# DSP28335.net
KiCad netlist of a schematic drawn in Altium Designer
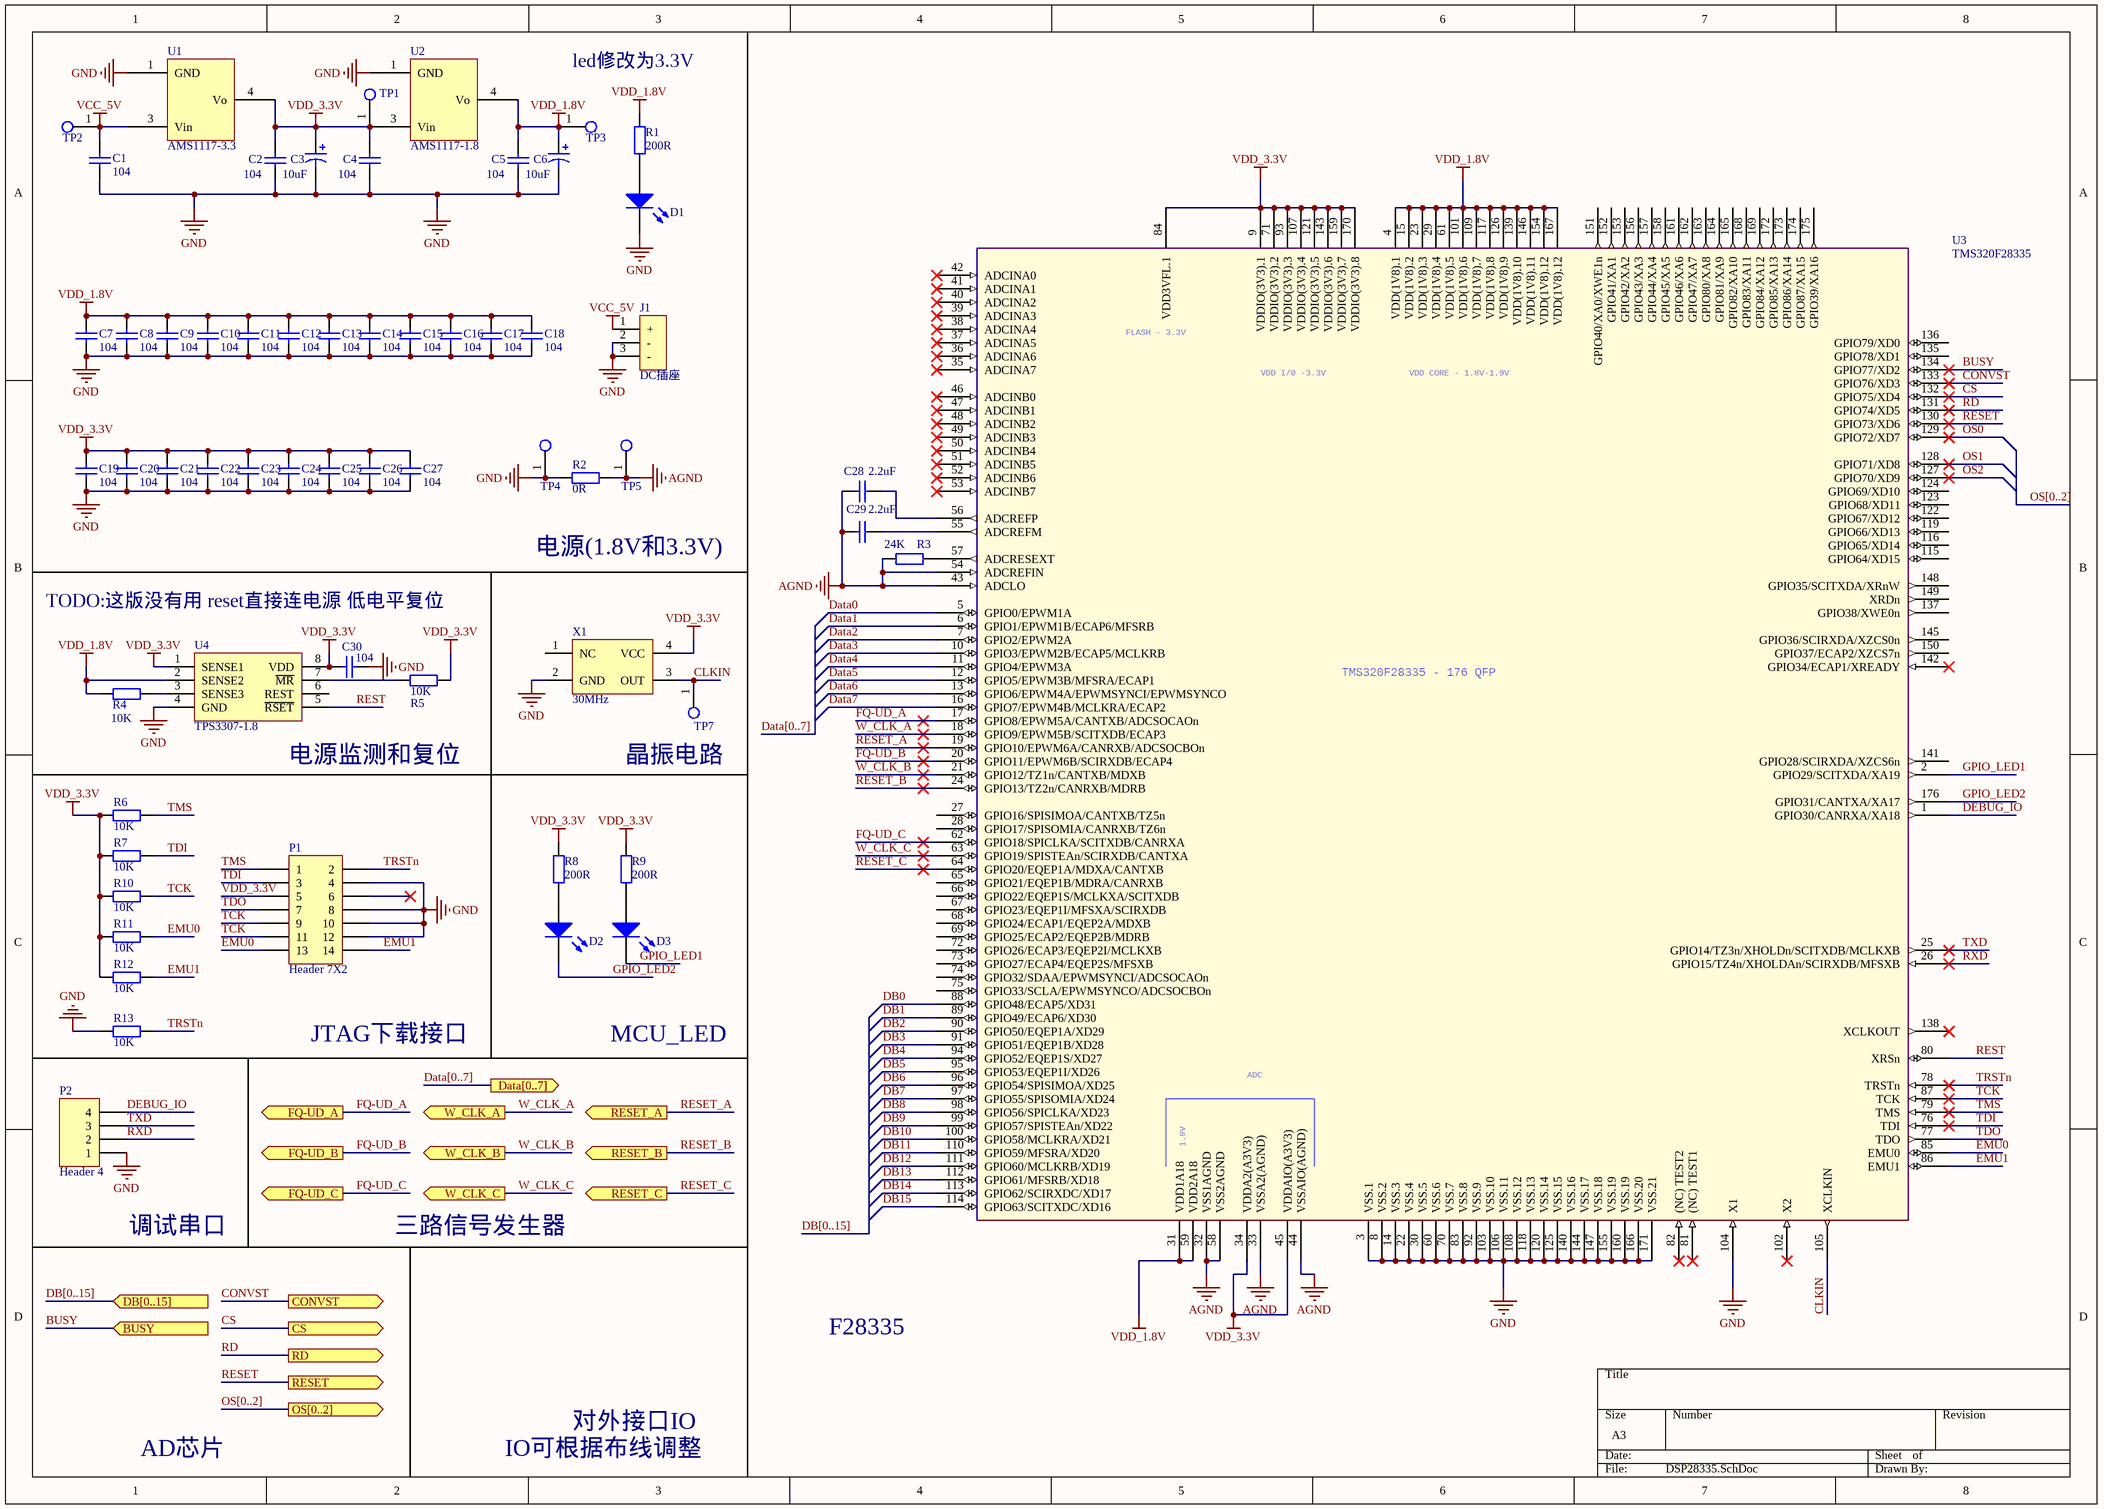
[diagram p0: DSP28335.SchDoc]

(export (version "E")
  (design (tool "Eeschema 10.0.6"))
  (components
    (comp (ref "C1")
      (value "104")
      (footprint "0603")
      (fields (field (name "Comment") "Cap"))
      (libsource (lib "自动化研究所集成库20170318") (part "Cap"))
    )
    (comp (ref "C2")
      (value "104")
      (footprint "0603")
      (fields (field (name "Comment") "Cap"))
      (libsource (lib "自动化研究所集成库20170318") (part "Cap"))
    )
    (comp (ref "C3")
      (value "10uF")
      (footprint "Cap 3528B")
      (fields (field (name "Comment") "Cap Poll"))
      (libsource (lib "自动化研究所集成库20170318") (part "Cap Poll"))
    )
    (comp (ref "C4")
      (value "104")
      (footprint "0603")
      (fields (field (name "Comment") "Cap"))
      (libsource (lib "自动化研究所集成库20170318") (part "Cap"))
    )
    (comp (ref "C5")
      (value "104")
      (footprint "0603")
      (fields (field (name "Comment") "Cap"))
      (libsource (lib "自动化研究所集成库20170318") (part "Cap"))
    )
    (comp (ref "C6")
      (value "10uF")
      (footprint "Cap 3528B")
      (fields (field (name "Comment") "Cap Poll"))
      (libsource (lib "自动化研究所集成库20170318") (part "Cap Poll"))
    )
    (comp (ref "C7")
      (value "104")
      (footprint "0603")
      (fields (field (name "Comment") "Cap"))
      (libsource (lib "自动化研究所集成库20170318") (part "Cap"))
    )
    (comp (ref "C8")
      (value "104")
      (footprint "0603")
      (fields (field (name "Comment") "Cap"))
      (libsource (lib "自动化研究所集成库20170318") (part "Cap"))
    )
    (comp (ref "C9")
      (value "104")
      (footprint "0603")
      (fields (field (name "Comment") "Cap"))
      (libsource (lib "自动化研究所集成库20170318") (part "Cap"))
    )
    (comp (ref "C10")
      (value "104")
      (footprint "0603")
      (fields (field (name "Comment") "Cap"))
      (libsource (lib "自动化研究所集成库20170318") (part "Cap"))
    )
    (comp (ref "C11")
      (value "104")
      (footprint "0603")
      (fields (field (name "Comment") "Cap"))
      (libsource (lib "自动化研究所集成库20170318") (part "Cap"))
    )
    (comp (ref "C12")
      (value "104")
      (footprint "0603")
      (fields (field (name "Comment") "Cap"))
      (libsource (lib "自动化研究所集成库20170318") (part "Cap"))
    )
    (comp (ref "C13")
      (value "104")
      (footprint "0603")
      (fields (field (name "Comment") "Cap"))
      (libsource (lib "自动化研究所集成库20170318") (part "Cap"))
    )
    (comp (ref "C14")
      (value "104")
      (footprint "0603")
      (fields (field (name "Comment") "Cap"))
      (libsource (lib "自动化研究所集成库20170318") (part "Cap"))
    )
    (comp (ref "C15")
      (value "104")
      (footprint "0603")
      (fields (field (name "Comment") "Cap"))
      (libsource (lib "自动化研究所集成库20170318") (part "Cap"))
    )
    (comp (ref "C16")
      (value "104")
      (footprint "0603")
      (fields (field (name "Comment") "Cap"))
      (libsource (lib "自动化研究所集成库20170318") (part "Cap"))
    )
    (comp (ref "C17")
      (value "104")
      (footprint "0603")
      (fields (field (name "Comment") "Cap"))
      (libsource (lib "自动化研究所集成库20170318") (part "Cap"))
    )
    (comp (ref "C18")
      (value "104")
      (footprint "0603")
      (fields (field (name "Comment") "Cap"))
      (libsource (lib "自动化研究所集成库20170318") (part "Cap"))
    )
    (comp (ref "C19")
      (value "104")
      (footprint "0603")
      (fields (field (name "Comment") "Cap"))
      (libsource (lib "自动化研究所集成库20170318") (part "Cap"))
    )
    (comp (ref "C20")
      (value "104")
      (footprint "0603")
      (fields (field (name "Comment") "Cap"))
      (libsource (lib "自动化研究所集成库20170318") (part "Cap"))
    )
    (comp (ref "C21")
      (value "104")
      (footprint "0603")
      (fields (field (name "Comment") "Cap"))
      (libsource (lib "自动化研究所集成库20170318") (part "Cap"))
    )
    (comp (ref "C22")
      (value "104")
      (footprint "0603")
      (fields (field (name "Comment") "Cap"))
      (libsource (lib "自动化研究所集成库20170318") (part "Cap"))
    )
    (comp (ref "C23")
      (value "104")
      (footprint "0603")
      (fields (field (name "Comment") "Cap"))
      (libsource (lib "自动化研究所集成库20170318") (part "Cap"))
    )
    (comp (ref "C24")
      (value "104")
      (footprint "0603")
      (fields (field (name "Comment") "Cap"))
      (libsource (lib "自动化研究所集成库20170318") (part "Cap"))
    )
    (comp (ref "C25")
      (value "104")
      (footprint "0603")
      (fields (field (name "Comment") "Cap"))
      (libsource (lib "自动化研究所集成库20170318") (part "Cap"))
    )
    (comp (ref "C26")
      (value "104")
      (footprint "0603")
      (fields (field (name "Comment") "Cap"))
      (libsource (lib "自动化研究所集成库20170318") (part "Cap"))
    )
    (comp (ref "C27")
      (value "104")
      (footprint "0603")
      (fields (field (name "Comment") "Cap"))
      (libsource (lib "自动化研究所集成库20170318") (part "Cap"))
    )
    (comp (ref "C28")
      (value "2.2uF")
      (footprint "0603")
      (fields (field (name "Comment") "Cap"))
      (libsource (lib "自动化研究所集成库20170318") (part "Cap"))
    )
    (comp (ref "C29")
      (value "2.2uF")
      (footprint "0603")
      (fields (field (name "Comment") "Cap"))
      (libsource (lib "自动化研究所集成库20170318") (part "Cap"))
    )
    (comp (ref "C30")
      (value "104")
      (footprint "0603")
      (fields (field (name "Comment") "Cap"))
      (libsource (lib "自动化研究所集成库20170318") (part "Cap"))
    )
    (comp (ref "D1") (value "LED") (footprint "LED0603") (libsource (lib "自动化研究所集成库20170318") (part "LED")))
    (comp (ref "D2") (value "LED") (footprint "LED0603") (libsource (lib "自动化研究所集成库20170318") (part "LED")))
    (comp (ref "D3") (value "LED") (footprint "LED0603") (libsource (lib "自动化研究所集成库20170318") (part "LED")))
    (comp (ref "J1")
      (value "DC插座")
      (footprint "DC插座 5.5mm*2.1mm")
      (libsource (lib "自动化研究所集成库20170318") (part "DC插座"))
    )
    (comp (ref "P1")
      (value "Header 7X2")
      (footprint "HDR2X7")
      (description "Header, 7-Pin, Dual row")
      (libsource (lib "Miscellaneous Connectors") (part "Header 7X2"))
    )
    (comp (ref "P2")
      (value "Header 4")
      (footprint "HDR1X4")
      (description "Header, 4-Pin")
      (libsource (lib "Miscellaneous Connectors") (part "Header 4"))
    )
    (comp (ref "R1")
      (value "200R")
      (footprint "0603")
      (fields (field (name "Comment") "Res"))
      (libsource (lib "") (part "Res_3"))
    )
    (comp (ref "R2")
      (value "0R")
      (footprint "0603")
      (fields (field (name "Comment") "Res"))
      (libsource (lib "") (part "Res_2"))
    )
    (comp (ref "R3")
      (value "24K")
      (footprint "0603")
      (fields (field (name "Comment") "Res"))
      (libsource (lib "自动化研究所集成库20170318") (part "Res"))
    )
    (comp (ref "R4")
      (value "10K")
      (footprint "0603")
      (fields (field (name "Comment") "Res"))
      (libsource (lib "") (part "Res_2"))
    )
    (comp (ref "R5")
      (value "10K")
      (footprint "0603")
      (fields (field (name "Comment") "Res"))
      (libsource (lib "自动化研究所集成库20170318") (part "Res"))
    )
    (comp (ref "R6")
      (value "10K")
      (footprint "0603")
      (fields (field (name "Comment") "Res"))
      (libsource (lib "自动化研究所集成库20170318") (part "Res"))
    )
    (comp (ref "R7")
      (value "10K")
      (footprint "0603")
      (fields (field (name "Comment") "Res"))
      (libsource (lib "自动化研究所集成库20170318") (part "Res"))
    )
    (comp (ref "R8")
      (value "200R")
      (footprint "0603")
      (fields (field (name "Comment") "Res"))
      (libsource (lib "") (part "Res_1"))
    )
    (comp (ref "R9")
      (value "200R")
      (footprint "0603")
      (fields (field (name "Comment") "Res"))
      (libsource (lib "") (part "Res_1"))
    )
    (comp (ref "R10")
      (value "10K")
      (footprint "0603")
      (fields (field (name "Comment") "Res"))
      (libsource (lib "自动化研究所集成库20170318") (part "Res"))
    )
    (comp (ref "R11")
      (value "10K")
      (footprint "0603")
      (fields (field (name "Comment") "Res"))
      (libsource (lib "自动化研究所集成库20170318") (part "Res"))
    )
    (comp (ref "R12")
      (value "10K")
      (footprint "0603")
      (fields (field (name "Comment") "Res"))
      (libsource (lib "自动化研究所集成库20170318") (part "Res"))
    )
    (comp (ref "R13")
      (value "10K")
      (footprint "0603")
      (fields (field (name "Comment") "Res"))
      (libsource (lib "自动化研究所集成库20170318") (part "Res"))
    )
    (comp (ref "TP1") (value "testPoint") (footprint "TP_H") (libsource (lib "Spartan") (part "TP")))
    (comp (ref "TP2") (value "testPoint") (footprint "TP_H") (libsource (lib "Spartan") (part "TP")))
    (comp (ref "TP3") (value "testPoint") (footprint "TP_H") (libsource (lib "Spartan") (part "TP")))
    (comp (ref "TP4") (value "testPoint") (footprint "TP_H") (libsource (lib "Spartan") (part "TP")))
    (comp (ref "TP5") (value "testPoint") (footprint "TP_H") (libsource (lib "Spartan") (part "TP")))
    (comp (ref "TP7") (value "testPoint") (footprint "TP_H") (libsource (lib "Spartan") (part "TP")))
    (comp (ref "U1")
      (value "AMS1117-3.3")
      (footprint "TO-252-2L")
      (libsource (lib "Spartan") (part "AMS1117"))
    )
    (comp (ref "U2")
      (value "AMS1117-1.8")
      (footprint "TO-252-2L")
      (libsource (lib "Spartan") (part "AMS1117"))
    )
    (comp (ref "U3")
      (value "TMS320F28335")
      (footprint "TMS320F28335")
      (libsource (lib "DuGu") (part "TMS320F28335"))
    )
    (comp (ref "U4") (value "TPS3307-1.8") (footprint "SOP-8") (libsource (lib "Dugu") (part "TPS3307-1.8")))
    (comp (ref "X1")
      (value "30MHz")
      (footprint "3225")
      (libsource (lib "PulsePower-Buck") (part "Oscillator"))
    )
  )
  (nets
    (net (code "1") (name "/BUSY") (class "Default")
      (node (ref "U3") (pin "134") (pinfunction "GPIO77/XD2_134") (pintype "bidirectional+no_connect"))
    )
    (net (code "2") (name "/CLKIN") (class "Default")
      (node (ref "TP7") (pin "1") (pinfunction "1_1") (pintype "passive"))
      (node (ref "U3") (pin "105") (pinfunction "XCLKIN_105") (pintype "output"))
      (node (ref "X1") (pin "3") (pinfunction "OUT_3") (pintype "passive"))
    )
    (net (code "3") (name "/CONVST") (class "Default")
      (node (ref "U3") (pin "133") (pinfunction "GPIO76/XD3_133") (pintype "bidirectional+no_connect"))
    )
    (net (code "4") (name "/CS") (class "Default")
      (node (ref "U3") (pin "132") (pinfunction "GPIO75/XD4_132") (pintype "bidirectional+no_connect"))
    )
    (net (code "5") (name "/DB0") (class "Default")
      (node (ref "U3") (pin "88") (pinfunction "GPIO48/ECAP5/XD31_88") (pintype "bidirectional"))
    )
    (net (code "6") (name "/DB1") (class "Default")
      (node (ref "U3") (pin "89") (pinfunction "GPIO49/ECAP6/XD30_89") (pintype "bidirectional"))
    )
    (net (code "7") (name "/DB2") (class "Default")
      (node (ref "U3") (pin "90") (pinfunction "GPIO50/EQEP1A/XD29_90") (pintype "bidirectional"))
    )
    (net (code "8") (name "/DB3") (class "Default")
      (node (ref "U3") (pin "91") (pinfunction "GPIO51/EQEP1B/XD28_91") (pintype "bidirectional"))
    )
    (net (code "9") (name "/DB4") (class "Default")
      (node (ref "U3") (pin "94") (pinfunction "GPIO52/EQEP1S/XD27_94") (pintype "bidirectional"))
    )
    (net (code "10") (name "/DB5") (class "Default")
      (node (ref "U3") (pin "95") (pinfunction "GPIO53/EQEP1I/XD26_95") (pintype "bidirectional"))
    )
    (net (code "11") (name "/DB6") (class "Default")
      (node (ref "U3") (pin "96") (pinfunction "GPIO54/SPISIMOA/XD25_96") (pintype "bidirectional"))
    )
    (net (code "12") (name "/DB7") (class "Default")
      (node (ref "U3") (pin "97") (pinfunction "GPIO55/SPISOMIA/XD24_97") (pintype "bidirectional"))
    )
    (net (code "13") (name "/DB8") (class "Default")
      (node (ref "U3") (pin "98") (pinfunction "GPIO56/SPICLKA/XD23_98") (pintype "bidirectional"))
    )
    (net (code "14") (name "/DB9") (class "Default")
      (node (ref "U3") (pin "99") (pinfunction "GPIO57/SPISTEAn/XD22_99") (pintype "bidirectional"))
    )
    (net (code "15") (name "/DB10") (class "Default")
      (node (ref "U3") (pin "100") (pinfunction "GPIO58/MCLKRA/XD21_100") (pintype "bidirectional"))
    )
    (net (code "16") (name "/DB11") (class "Default")
      (node (ref "U3") (pin "110") (pinfunction "GPIO59/MFSRA/XD20_110") (pintype "bidirectional"))
    )
    (net (code "17") (name "/DB12") (class "Default")
      (node (ref "U3") (pin "111") (pinfunction "GPIO60/MCLKRB/XD19_111") (pintype "bidirectional"))
    )
    (net (code "18") (name "/DB13") (class "Default")
      (node (ref "U3") (pin "112") (pinfunction "GPIO61/MFSRB/XD18_112") (pintype "bidirectional"))
    )
    (net (code "19") (name "/DB14") (class "Default")
      (node (ref "U3") (pin "113") (pinfunction "GPIO62/SCIRXDC/XD17_113") (pintype "bidirectional"))
    )
    (net (code "20") (name "/DB15") (class "Default")
      (node (ref "U3") (pin "114") (pinfunction "GPIO63/SCITXDC/XD16_114") (pintype "bidirectional"))
    )
    (net (code "22") (name "/DEBUG_IO") (class "Default")
      (node (ref "P2") (pin "4") (pinfunction "4_4") (pintype "passive"))
      (node (ref "U3") (pin "1") (pinfunction "GPIO30/CANRXA/XA18_1") (pintype "output"))
    )
    (net (code "23") (name "/Data0") (class "Default")
      (node (ref "U3") (pin "5") (pinfunction "GPIO0/EPWM1A_5") (pintype "bidirectional"))
    )
    (net (code "24") (name "/Data1") (class "Default")
      (node (ref "U3") (pin "6") (pinfunction "GPIO1/EPWM1B/ECAP6/MFSRB_6") (pintype "bidirectional"))
    )
    (net (code "25") (name "/Data2") (class "Default")
      (node (ref "U3") (pin "7") (pinfunction "GPIO2/EPWM2A_7") (pintype "bidirectional"))
    )
    (net (code "26") (name "/Data3") (class "Default")
      (node (ref "U3") (pin "10") (pinfunction "GPIO3/EPWM2B/ECAP5/MCLKRB_10") (pintype "bidirectional"))
    )
    (net (code "27") (name "/Data4") (class "Default")
      (node (ref "U3") (pin "11") (pinfunction "GPIO4/EPWM3A_11") (pintype "bidirectional"))
    )
    (net (code "28") (name "/Data5") (class "Default")
      (node (ref "U3") (pin "12") (pinfunction "GPIO5/EPWM3B/MFSRA/ECAP1_12") (pintype "bidirectional"))
    )
    (net (code "29") (name "/Data6") (class "Default")
      (node (ref "U3") (pin "13") (pinfunction "GPIO6/EPWM4A/EPWMSYNCI/EPWMSYNCO_13") (pintype "bidirectional"))
    )
    (net (code "30") (name "/Data7") (class "Default")
      (node (ref "U3") (pin "16") (pinfunction "GPIO7/EPWM4B/MCLKRA/ECAP2_16") (pintype "bidirectional"))
    )
    (net (code "32") (name "/EMU0") (class "Default")
      (node (ref "P1") (pin "13") (pinfunction "13_13") (pintype "passive"))
      (node (ref "R11") (pin "2") (pinfunction "2_2") (pintype "passive"))
      (node (ref "U3") (pin "85") (pinfunction "EMU0_85") (pintype "bidirectional"))
    )
    (net (code "33") (name "/EMU1") (class "Default")
      (node (ref "P1") (pin "14") (pinfunction "14_14") (pintype "passive"))
      (node (ref "R12") (pin "2") (pinfunction "2_2") (pintype "passive"))
      (node (ref "U3") (pin "86") (pinfunction "EMU1_86") (pintype "bidirectional"))
    )
    (net (code "34") (name "/FQ-UD_A") (class "Default")
      (node (ref "U3") (pin "17") (pinfunction "GPIO8/EPWM5A/CANTXB/ADCSOCAOn_17") (pintype "bidirectional"))
    )
    (net (code "35") (name "/FQ-UD_B") (class "Default")
      (node (ref "U3") (pin "20") (pinfunction "GPIO11/EPWM6B/SCIRXDB/ECAP4_20") (pintype "bidirectional"))
    )
    (net (code "36") (name "/FQ-UD_C") (class "Default")
      (node (ref "U3") (pin "62") (pinfunction "GPIO18/SPICLKA/SCITXDB/CANRXA_62") (pintype "bidirectional"))
    )
    (net (code "37") (name "/GPIO_LED1") (class "Default")
      (node (ref "D3") (pin "2") (pinfunction "K_2") (pintype "passive"))
      (node (ref "U3") (pin "2") (pinfunction "GPIO29/SCITXDA/XA19_2") (pintype "output"))
    )
    (net (code "38") (name "/GPIO_LED2") (class "Default")
      (node (ref "D2") (pin "2") (pinfunction "K_2") (pintype "passive"))
      (node (ref "U3") (pin "176") (pinfunction "GPIO31/CANTXA/XA17_176") (pintype "output"))
    )
    (net (code "39") (name "/OS0") (class "Default")
      (node (ref "U3") (pin "129") (pinfunction "GPIO72/XD7_129") (pintype "bidirectional+no_connect"))
    )
    (net (code "40") (name "/OS1") (class "Default")
      (node (ref "U3") (pin "128") (pinfunction "GPIO71/XD8_128") (pintype "bidirectional+no_connect"))
    )
    (net (code "41") (name "/OS2") (class "Default")
      (node (ref "U3") (pin "127") (pinfunction "GPIO70/XD9_127") (pintype "bidirectional+no_connect"))
    )
    (net (code "43") (name "/RD") (class "Default")
      (node (ref "U3") (pin "131") (pinfunction "GPIO74/XD5_131") (pintype "bidirectional+no_connect"))
    )
    (net (code "44") (name "/RESET") (class "Default")
      (node (ref "U3") (pin "130") (pinfunction "GPIO73/XD6_130") (pintype "bidirectional+no_connect"))
    )
    (net (code "45") (name "/RESET_A") (class "Default")
      (node (ref "U3") (pin "19") (pinfunction "GPIO10/EPWM6A/CANRXB/ADCSOCBOn_19") (pintype "bidirectional"))
    )
    (net (code "46") (name "/RESET_B") (class "Default")
      (node (ref "U3") (pin "24") (pinfunction "GPIO13/TZ2n/CANRXB/MDRB_24") (pintype "bidirectional"))
    )
    (net (code "47") (name "/RESET_C") (class "Default")
      (node (ref "U3") (pin "64") (pinfunction "GPIO20/EQEP1A/MDXA/CANTXB_64") (pintype "bidirectional"))
    )
    (net (code "48") (name "/REST") (class "Default")
      (node (ref "U3") (pin "80") (pinfunction "XRSn_80") (pintype "bidirectional"))
      (node (ref "U4") (pin "5") (pinfunction "~{RSET}_5") (pintype "passive"))
    )
    (net (code "49") (name "/RXD") (class "Default")
      (node (ref "P2") (pin "2") (pinfunction "2_2") (pintype "passive"))
      (node (ref "U3") (pin "26") (pinfunction "GPIO15/TZ4n/XHOLDAn/SCIRXDB/MFSXB_26") (pintype "input"))
    )
    (net (code "50") (name "/TCK") (class "Default")
      (node (ref "P1") (pin "11") (pinfunction "11_11") (pintype "passive"))
      (node (ref "P1") (pin "9") (pinfunction "9_9") (pintype "passive"))
      (node (ref "R10") (pin "2") (pinfunction "2_2") (pintype "passive"))
      (node (ref "U3") (pin "87") (pinfunction "TCK_87") (pintype "input"))
    )
    (net (code "51") (name "/TDI") (class "Default")
      (node (ref "P1") (pin "3") (pinfunction "3_3") (pintype "passive"))
      (node (ref "R7") (pin "2") (pinfunction "2_2") (pintype "passive"))
      (node (ref "U3") (pin "76") (pinfunction "TDI_76") (pintype "input"))
    )
    (net (code "52") (name "/TDO") (class "Default")
      (node (ref "P1") (pin "7") (pinfunction "7_7") (pintype "passive"))
      (node (ref "U3") (pin "77") (pinfunction "TDO_77") (pintype "output"))
    )
    (net (code "53") (name "/TMS") (class "Default")
      (node (ref "P1") (pin "1") (pinfunction "1_1") (pintype "passive"))
      (node (ref "R6") (pin "2") (pinfunction "2_2") (pintype "passive"))
      (node (ref "U3") (pin "79") (pinfunction "TMS_79") (pintype "input"))
    )
    (net (code "54") (name "/TRSTn") (class "Default")
      (node (ref "P1") (pin "2") (pinfunction "2_2") (pintype "passive"))
      (node (ref "R13") (pin "2") (pinfunction "2_2") (pintype "passive"))
      (node (ref "U3") (pin "78") (pinfunction "TRSTn_78") (pintype "input"))
    )
    (net (code "55") (name "/TXD") (class "Default")
      (node (ref "P2") (pin "3") (pinfunction "3_3") (pintype "passive"))
      (node (ref "U3") (pin "25") (pinfunction "GPIO14/TZ3n/XHOLDn/SCITXDB/MCLKXB_25") (pintype "output"))
    )
    (net (code "56") (name "/W_CLK_A") (class "Default")
      (node (ref "U3") (pin "18") (pinfunction "GPIO9/EPWM5B/SCITXDB/ECAP3_18") (pintype "bidirectional"))
    )
    (net (code "57") (name "/W_CLK_B") (class "Default")
      (node (ref "U3") (pin "21") (pinfunction "GPIO12/TZ1n/CANTXB/MDXB_21") (pintype "bidirectional"))
    )
    (net (code "58") (name "/W_CLK_C") (class "Default")
      (node (ref "U3") (pin "63") (pinfunction "GPIO19/SPISTEAn/SCIRXDB/CANTXA_63") (pintype "bidirectional"))
    )
    (net (code "59") (name "AGND") (class "Default")
      (node (ref "C28") (pin "2") (pinfunction "2_2") (pintype "passive"))
      (node (ref "C29") (pin "2") (pinfunction "2_2") (pintype "passive"))
      (node (ref "R2") (pin "1") (pinfunction "1_1") (pintype "passive"))
      (node (ref "R3") (pin "1") (pinfunction "1_1") (pintype "passive"))
      (node (ref "TP5") (pin "1") (pinfunction "1_1") (pintype "passive"))
      (node (ref "U3") (pin "32") (pinfunction "VSS1AGND_32") (pintype "power_in"))
      (node (ref "U3") (pin "33") (pinfunction "VSSA2(AGND)_33") (pintype "power_in"))
      (node (ref "U3") (pin "43") (pinfunction "ADCLO_43") (pintype "input"))
      (node (ref "U3") (pin "44") (pinfunction "VSSAIO(AGND)_44") (pintype "power_in"))
      (node (ref "U3") (pin "54") (pinfunction "ADCREFIN_54") (pintype "input"))
      (node (ref "U3") (pin "58") (pinfunction "VSS2AGND_58") (pintype "power_in"))
    )
    (net (code "60") (name "GND") (class "Default")
      (node (ref "C1") (pin "1") (pinfunction "1_1") (pintype "passive"))
      (node (ref "C10") (pin "1") (pinfunction "1_1") (pintype "passive"))
      (node (ref "C11") (pin "1") (pinfunction "1_1") (pintype "passive"))
      (node (ref "C12") (pin "1") (pinfunction "1_1") (pintype "passive"))
      (node (ref "C13") (pin "1") (pinfunction "1_1") (pintype "passive"))
      (node (ref "C14") (pin "1") (pinfunction "1_1") (pintype "passive"))
      (node (ref "C15") (pin "1") (pinfunction "1_1") (pintype "passive"))
      (node (ref "C16") (pin "1") (pinfunction "1_1") (pintype "passive"))
      (node (ref "C17") (pin "1") (pinfunction "1_1") (pintype "passive"))
      (node (ref "C18") (pin "1") (pinfunction "1_1") (pintype "passive"))
      (node (ref "C19") (pin "1") (pinfunction "1_1") (pintype "passive"))
      (node (ref "C2") (pin "1") (pinfunction "1_1") (pintype "passive"))
      (node (ref "C20") (pin "1") (pinfunction "1_1") (pintype "passive"))
      (node (ref "C21") (pin "1") (pinfunction "1_1") (pintype "passive"))
      (node (ref "C22") (pin "1") (pinfunction "1_1") (pintype "passive"))
      (node (ref "C23") (pin "1") (pinfunction "1_1") (pintype "passive"))
      (node (ref "C24") (pin "1") (pinfunction "1_1") (pintype "passive"))
      (node (ref "C25") (pin "1") (pinfunction "1_1") (pintype "passive"))
      (node (ref "C26") (pin "1") (pinfunction "1_1") (pintype "passive"))
      (node (ref "C27") (pin "1") (pinfunction "1_1") (pintype "passive"))
      (node (ref "C3") (pin "2") (pinfunction "2_2") (pintype "passive"))
      (node (ref "C30") (pin "1") (pinfunction "1_1") (pintype "passive"))
      (node (ref "C4") (pin "1") (pinfunction "1_1") (pintype "passive"))
      (node (ref "C5") (pin "1") (pinfunction "1_1") (pintype "passive"))
      (node (ref "C6") (pin "2") (pinfunction "2_2") (pintype "passive"))
      (node (ref "C7") (pin "1") (pinfunction "1_1") (pintype "passive"))
      (node (ref "C8") (pin "1") (pinfunction "1_1") (pintype "passive"))
      (node (ref "C9") (pin "1") (pinfunction "1_1") (pintype "passive"))
      (node (ref "D1") (pin "2") (pinfunction "K_2") (pintype "passive"))
      (node (ref "J1") (pin "2") (pinfunction "-_2") (pintype "power_in"))
      (node (ref "J1") (pin "3") (pinfunction "-_3") (pintype "power_in"))
      (node (ref "P1") (pin "10") (pinfunction "10_10") (pintype "passive"))
      (node (ref "P1") (pin "12") (pinfunction "12_12") (pintype "passive"))
      (node (ref "P1") (pin "4") (pinfunction "4_4") (pintype "passive"))
      (node (ref "P1") (pin "8") (pinfunction "8_8") (pintype "passive"))
      (node (ref "P2") (pin "1") (pinfunction "1_1") (pintype "passive"))
      (node (ref "R13") (pin "1") (pinfunction "1_1") (pintype "passive"))
      (node (ref "R2") (pin "2") (pinfunction "2_2") (pintype "passive"))
      (node (ref "TP4") (pin "1") (pinfunction "1_1") (pintype "passive"))
      (node (ref "U1") (pin "1") (pinfunction "GND_1") (pintype "passive"))
      (node (ref "U2") (pin "1") (pinfunction "GND_1") (pintype "passive"))
      (node (ref "U3") (pin "103") (pinfunction "VSS.10_103") (pintype "power_in"))
      (node (ref "U3") (pin "104") (pinfunction "X1_104") (pintype "input"))
      (node (ref "U3") (pin "106") (pinfunction "VSS.11_106") (pintype "power_in"))
      (node (ref "U3") (pin "108") (pinfunction "VSS.12_108") (pintype "power_in"))
      (node (ref "U3") (pin "118") (pinfunction "VSS.13_118") (pintype "power_in"))
      (node (ref "U3") (pin "120") (pinfunction "VSS.14_120") (pintype "power_in"))
      (node (ref "U3") (pin "125") (pinfunction "VSS.15_125") (pintype "power_in"))
      (node (ref "U3") (pin "14") (pinfunction "VSS.3_14") (pintype "power_in"))
      (node (ref "U3") (pin "140") (pinfunction "VSS.16_140") (pintype "power_in"))
      (node (ref "U3") (pin "144") (pinfunction "VSS.17_144") (pintype "power_in"))
      (node (ref "U3") (pin "147") (pinfunction "VSS.18_147") (pintype "power_in"))
      (node (ref "U3") (pin "155") (pinfunction "VSS.19_155") (pintype "power_in"))
      (node (ref "U3") (pin "160") (pinfunction "VSS.19_160") (pintype "power_in"))
      (node (ref "U3") (pin "166") (pinfunction "VSS.20_166") (pintype "power_in"))
      (node (ref "U3") (pin "171") (pinfunction "VSS.21_171") (pintype "power_in"))
      (node (ref "U3") (pin "22") (pinfunction "VSS.4_22") (pintype "power_in"))
      (node (ref "U3") (pin "3") (pinfunction "VSS.1_3") (pintype "power_in"))
      (node (ref "U3") (pin "30") (pinfunction "VSS.5_30") (pintype "power_in"))
      (node (ref "U3") (pin "60") (pinfunction "VSS.6_60") (pintype "power_in"))
      (node (ref "U3") (pin "70") (pinfunction "VSS.7_70") (pintype "power_in"))
      (node (ref "U3") (pin "8") (pinfunction "VSS.2_8") (pintype "power_in"))
      (node (ref "U3") (pin "83") (pinfunction "VSS.8_83") (pintype "power_in"))
      (node (ref "U3") (pin "92") (pinfunction "VSS.9_92") (pintype "power_in"))
      (node (ref "U4") (pin "4") (pinfunction "GND_4") (pintype "passive"))
      (node (ref "X1") (pin "2") (pinfunction "GND_2") (pintype "passive"))
    )
    (net (code "61") (name "Net-(D1-A)") (class "Default")
      (node (ref "D1") (pin "1") (pinfunction "A_1") (pintype "passive"))
      (node (ref "R1") (pin "1") (pinfunction "1_1") (pintype "passive"))
    )
    (net (code "62") (name "Net-(D2-A)") (class "Default")
      (node (ref "D2") (pin "1") (pinfunction "A_1") (pintype "passive"))
      (node (ref "R8") (pin "2") (pinfunction "2_2") (pintype "passive"))
    )
    (net (code "63") (name "Net-(D3-A)") (class "Default")
      (node (ref "D3") (pin "1") (pinfunction "A_1") (pintype "passive"))
      (node (ref "R9") (pin "2") (pinfunction "2_2") (pintype "passive"))
    )
    (net (code "64") (name "Net-(U3-ADCREFM)") (class "Default")
      (node (ref "C29") (pin "1") (pinfunction "1_1") (pintype "passive"))
      (node (ref "U3") (pin "55") (pinfunction "ADCREFM_55") (pintype "output"))
    )
    (net (code "65") (name "Net-(U3-ADCREFP)") (class "Default")
      (node (ref "C28") (pin "1") (pinfunction "1_1") (pintype "passive"))
      (node (ref "U3") (pin "56") (pinfunction "ADCREFP_56") (pintype "output"))
    )
    (net (code "66") (name "Net-(U3-ADCRESEXT)") (class "Default")
      (node (ref "R3") (pin "2") (pinfunction "2_2") (pintype "passive"))
      (node (ref "U3") (pin "57") (pinfunction "ADCRESEXT_57") (pintype "output"))
    )
    (net (code "67") (name "Net-(U4-SENSE3)") (class "Default")
      (node (ref "R4") (pin "1") (pinfunction "1_1") (pintype "passive"))
      (node (ref "U4") (pin "3") (pinfunction "SENSE3_3") (pintype "passive"))
    )
    (net (code "68") (name "Net-(U4-~{MR})") (class "Default")
      (node (ref "R5") (pin "1") (pinfunction "1_1") (pintype "passive"))
      (node (ref "U4") (pin "7") (pinfunction "~{MR}_7") (pintype "passive"))
    )
    (net (code "69") (name "VCC_5V") (class "Default")
      (node (ref "C1") (pin "2") (pinfunction "2_2") (pintype "passive"))
      (node (ref "J1") (pin "1") (pinfunction "+_1") (pintype "power_in"))
      (node (ref "TP2") (pin "1") (pinfunction "1_1") (pintype "passive"))
      (node (ref "U1") (pin "3") (pinfunction "Vin_3") (pintype "passive"))
    )
    (net (code "70") (name "VDD_1.8V") (class "Default")
      (node (ref "C10") (pin "2") (pinfunction "2_2") (pintype "passive"))
      (node (ref "C11") (pin "2") (pinfunction "2_2") (pintype "passive"))
      (node (ref "C12") (pin "2") (pinfunction "2_2") (pintype "passive"))
      (node (ref "C13") (pin "2") (pinfunction "2_2") (pintype "passive"))
      (node (ref "C14") (pin "2") (pinfunction "2_2") (pintype "passive"))
      (node (ref "C15") (pin "2") (pinfunction "2_2") (pintype "passive"))
      (node (ref "C16") (pin "2") (pinfunction "2_2") (pintype "passive"))
      (node (ref "C17") (pin "2") (pinfunction "2_2") (pintype "passive"))
      (node (ref "C18") (pin "2") (pinfunction "2_2") (pintype "passive"))
      (node (ref "C5") (pin "2") (pinfunction "2_2") (pintype "passive"))
      (node (ref "C6") (pin "1") (pinfunction "1_1") (pintype "passive"))
      (node (ref "C7") (pin "2") (pinfunction "2_2") (pintype "passive"))
      (node (ref "C8") (pin "2") (pinfunction "2_2") (pintype "passive"))
      (node (ref "C9") (pin "2") (pinfunction "2_2") (pintype "passive"))
      (node (ref "R1") (pin "2") (pinfunction "2_2") (pintype "passive"))
      (node (ref "R4") (pin "2") (pinfunction "2_2") (pintype "passive"))
      (node (ref "TP3") (pin "1") (pinfunction "1_1") (pintype "passive"))
      (node (ref "U2") (pin "4") (pinfunction "Vo_4") (pintype "passive"))
      (node (ref "U3") (pin "101") (pinfunction "VDD(1V8).6_101") (pintype "power_in"))
      (node (ref "U3") (pin "109") (pinfunction "VDD(1V8).7_109") (pintype "power_in"))
      (node (ref "U3") (pin "117") (pinfunction "VDD(1V8).8_117") (pintype "power_in"))
      (node (ref "U3") (pin "126") (pinfunction "VDD(1V8).9_126") (pintype "power_in"))
      (node (ref "U3") (pin "139") (pinfunction "VDD(1V8).10_139") (pintype "power_in"))
      (node (ref "U3") (pin "146") (pinfunction "VDD(1V8).11_146") (pintype "power_in"))
      (node (ref "U3") (pin "15") (pinfunction "VDD(1V8).2_15") (pintype "power_in"))
      (node (ref "U3") (pin "154") (pinfunction "VDD(1V8).12_154") (pintype "power_in"))
      (node (ref "U3") (pin "167") (pinfunction "VDD(1V8).12_167") (pintype "power_in"))
      (node (ref "U3") (pin "23") (pinfunction "VDD(1V8).3_23") (pintype "power_in"))
      (node (ref "U3") (pin "29") (pinfunction "VDD(1V8).4_29") (pintype "power_in"))
      (node (ref "U3") (pin "31") (pinfunction "VDD1A18_31") (pintype "power_in"))
      (node (ref "U3") (pin "4") (pinfunction "VDD(1V8).1_4") (pintype "power_in"))
      (node (ref "U3") (pin "59") (pinfunction "VDD2A18_59") (pintype "power_in"))
      (node (ref "U3") (pin "61") (pinfunction "VDD(1V8).5_61") (pintype "power_in"))
      (node (ref "U4") (pin "2") (pinfunction "SENSE2_2") (pintype "passive"))
    )
    (net (code "71") (name "VDD_3.3V") (class "Default")
      (node (ref "C19") (pin "2") (pinfunction "2_2") (pintype "passive"))
      (node (ref "C2") (pin "2") (pinfunction "2_2") (pintype "passive"))
      (node (ref "C20") (pin "2") (pinfunction "2_2") (pintype "passive"))
      (node (ref "C21") (pin "2") (pinfunction "2_2") (pintype "passive"))
      (node (ref "C22") (pin "2") (pinfunction "2_2") (pintype "passive"))
      (node (ref "C23") (pin "2") (pinfunction "2_2") (pintype "passive"))
      (node (ref "C24") (pin "2") (pinfunction "2_2") (pintype "passive"))
      (node (ref "C25") (pin "2") (pinfunction "2_2") (pintype "passive"))
      (node (ref "C26") (pin "2") (pinfunction "2_2") (pintype "passive"))
      (node (ref "C27") (pin "2") (pinfunction "2_2") (pintype "passive"))
      (node (ref "C3") (pin "1") (pinfunction "1_1") (pintype "passive"))
      (node (ref "C30") (pin "2") (pinfunction "2_2") (pintype "passive"))
      (node (ref "C4") (pin "2") (pinfunction "2_2") (pintype "passive"))
      (node (ref "P1") (pin "5") (pinfunction "5_5") (pintype "passive"))
      (node (ref "R10") (pin "1") (pinfunction "1_1") (pintype "passive"))
      (node (ref "R11") (pin "1") (pinfunction "1_1") (pintype "passive"))
      (node (ref "R12") (pin "1") (pinfunction "1_1") (pintype "passive"))
      (node (ref "R5") (pin "2") (pinfunction "2_2") (pintype "passive"))
      (node (ref "R6") (pin "1") (pinfunction "1_1") (pintype "passive"))
      (node (ref "R7") (pin "1") (pinfunction "1_1") (pintype "passive"))
      (node (ref "R8") (pin "1") (pinfunction "1_1") (pintype "passive"))
      (node (ref "R9") (pin "1") (pinfunction "1_1") (pintype "passive"))
      (node (ref "TP1") (pin "1") (pinfunction "1_1") (pintype "passive"))
      (node (ref "U1") (pin "4") (pinfunction "Vo_4") (pintype "passive"))
      (node (ref "U2") (pin "3") (pinfunction "Vin_3") (pintype "passive"))
      (node (ref "U3") (pin "107") (pinfunction "VDDIO(3V3).4_107") (pintype "power_in"))
      (node (ref "U3") (pin "121") (pinfunction "VDDIO(3V3).5_121") (pintype "power_in"))
      (node (ref "U3") (pin "143") (pinfunction "VDDIO(3V3).6_143") (pintype "power_in"))
      (node (ref "U3") (pin "159") (pinfunction "VDDIO(3V3).7_159") (pintype "power_in"))
      (node (ref "U3") (pin "170") (pinfunction "VDDIO(3V3).8_170") (pintype "power_in"))
      (node (ref "U3") (pin "34") (pinfunction "VDDA2(A3V3)_34") (pintype "power_in"))
      (node (ref "U3") (pin "45") (pinfunction "VDDAIO(A3V3)_45") (pintype "power_in"))
      (node (ref "U3") (pin "71") (pinfunction "VDDIO(3V3).2_71") (pintype "power_in"))
      (node (ref "U3") (pin "84") (pinfunction "VDD3VFL.1_84") (pintype "power_in"))
      (node (ref "U3") (pin "9") (pinfunction "VDDIO(3V3).1_9") (pintype "power_in"))
      (node (ref "U3") (pin "93") (pinfunction "VDDIO(3V3).3_93") (pintype "power_in"))
      (node (ref "U4") (pin "1") (pinfunction "SENSE1_1") (pintype "passive"))
      (node (ref "U4") (pin "8") (pinfunction "VDD_8") (pintype "passive"))
      (node (ref "X1") (pin "4") (pinfunction "VCC_4") (pintype "passive"))
    )
    (net (code "72") (name "unconnected-(P1-Pad6)") (class "Default")
      (node (ref "P1") (pin "6") (pinfunction "6_6") (pintype "passive+no_connect"))
    )
    (net (code "73") (name "unconnected-(U3-(NC)_TEST1-Pad81)") (class "Default")
      (node (ref "U3") (pin "81") (pinfunction "(NC)_TEST1_81") (pintype "input+no_connect"))
    )
    (net (code "74") (name "unconnected-(U3-(NC)_TEST2-Pad82)") (class "Default")
      (node (ref "U3") (pin "82") (pinfunction "(NC)_TEST2_82") (pintype "input+no_connect"))
    )
    (net (code "75") (name "unconnected-(U3-ADCINA0-Pad42)") (class "Default")
      (node (ref "U3") (pin "42") (pinfunction "ADCINA0_42") (pintype "input+no_connect"))
    )
    (net (code "76") (name "unconnected-(U3-ADCINA1-Pad41)") (class "Default")
      (node (ref "U3") (pin "41") (pinfunction "ADCINA1_41") (pintype "input+no_connect"))
    )
    (net (code "77") (name "unconnected-(U3-ADCINA2-Pad40)") (class "Default")
      (node (ref "U3") (pin "40") (pinfunction "ADCINA2_40") (pintype "input+no_connect"))
    )
    (net (code "78") (name "unconnected-(U3-ADCINA3-Pad39)") (class "Default")
      (node (ref "U3") (pin "39") (pinfunction "ADCINA3_39") (pintype "input+no_connect"))
    )
    (net (code "79") (name "unconnected-(U3-ADCINA4-Pad38)") (class "Default")
      (node (ref "U3") (pin "38") (pinfunction "ADCINA4_38") (pintype "input+no_connect"))
    )
    (net (code "80") (name "unconnected-(U3-ADCINA5-Pad37)") (class "Default")
      (node (ref "U3") (pin "37") (pinfunction "ADCINA5_37") (pintype "input+no_connect"))
    )
    (net (code "81") (name "unconnected-(U3-ADCINA6-Pad36)") (class "Default")
      (node (ref "U3") (pin "36") (pinfunction "ADCINA6_36") (pintype "input+no_connect"))
    )
    (net (code "82") (name "unconnected-(U3-ADCINA7-Pad35)") (class "Default")
      (node (ref "U3") (pin "35") (pinfunction "ADCINA7_35") (pintype "input+no_connect"))
    )
    (net (code "83") (name "unconnected-(U3-ADCINB0-Pad46)") (class "Default")
      (node (ref "U3") (pin "46") (pinfunction "ADCINB0_46") (pintype "input+no_connect"))
    )
    (net (code "84") (name "unconnected-(U3-ADCINB1-Pad47)") (class "Default")
      (node (ref "U3") (pin "47") (pinfunction "ADCINB1_47") (pintype "input+no_connect"))
    )
    (net (code "85") (name "unconnected-(U3-ADCINB2-Pad48)") (class "Default")
      (node (ref "U3") (pin "48") (pinfunction "ADCINB2_48") (pintype "input+no_connect"))
    )
    (net (code "86") (name "unconnected-(U3-ADCINB3-Pad49)") (class "Default")
      (node (ref "U3") (pin "49") (pinfunction "ADCINB3_49") (pintype "input+no_connect"))
    )
    (net (code "87") (name "unconnected-(U3-ADCINB4-Pad50)") (class "Default")
      (node (ref "U3") (pin "50") (pinfunction "ADCINB4_50") (pintype "input+no_connect"))
    )
    (net (code "88") (name "unconnected-(U3-ADCINB5-Pad51)") (class "Default")
      (node (ref "U3") (pin "51") (pinfunction "ADCINB5_51") (pintype "input+no_connect"))
    )
    (net (code "89") (name "unconnected-(U3-ADCINB6-Pad52)") (class "Default")
      (node (ref "U3") (pin "52") (pinfunction "ADCINB6_52") (pintype "input+no_connect"))
    )
    (net (code "90") (name "unconnected-(U3-ADCINB7-Pad53)") (class "Default")
      (node (ref "U3") (pin "53") (pinfunction "ADCINB7_53") (pintype "input+no_connect"))
    )
    (net (code "91") (name "unconnected-(U3-GPIO16{slash}SPISIMOA{slash}CANTXB{slash}TZ5n-Pad27)") (class "Default")
      (node (ref "U3") (pin "27") (pinfunction "GPIO16/SPISIMOA/CANTXB/TZ5n_27") (pintype "bidirectional"))
    )
    (net (code "92") (name "unconnected-(U3-GPIO17{slash}SPISOMIA{slash}CANRXB{slash}TZ6n-Pad28)") (class "Default")
      (node (ref "U3") (pin "28") (pinfunction "GPIO17/SPISOMIA/CANRXB/TZ6n_28") (pintype "bidirectional"))
    )
    (net (code "93") (name "unconnected-(U3-GPIO21{slash}EQEP1B{slash}MDRA{slash}CANRXB-Pad65)") (class "Default")
      (node (ref "U3") (pin "65") (pinfunction "GPIO21/EQEP1B/MDRA/CANRXB_65") (pintype "bidirectional"))
    )
    (net (code "94") (name "unconnected-(U3-GPIO22{slash}EQEP1S{slash}MCLKXA{slash}SCITXDB-Pad66)") (class "Default")
      (node (ref "U3") (pin "66") (pinfunction "GPIO22/EQEP1S/MCLKXA/SCITXDB_66") (pintype "bidirectional"))
    )
    (net (code "95") (name "unconnected-(U3-GPIO23{slash}EQEP1I{slash}MFSXA{slash}SCIRXDB-Pad67)") (class "Default")
      (node (ref "U3") (pin "67") (pinfunction "GPIO23/EQEP1I/MFSXA/SCIRXDB_67") (pintype "bidirectional"))
    )
    (net (code "96") (name "unconnected-(U3-GPIO24{slash}ECAP1{slash}EQEP2A{slash}MDXB-Pad68)") (class "Default")
      (node (ref "U3") (pin "68") (pinfunction "GPIO24/ECAP1/EQEP2A/MDXB_68") (pintype "bidirectional"))
    )
    (net (code "97") (name "unconnected-(U3-GPIO25{slash}ECAP2{slash}EQEP2B{slash}MDRB-Pad69)") (class "Default")
      (node (ref "U3") (pin "69") (pinfunction "GPIO25/ECAP2/EQEP2B/MDRB_69") (pintype "bidirectional"))
    )
    (net (code "98") (name "unconnected-(U3-GPIO26{slash}ECAP3{slash}EQEP2I{slash}MCLKXB-Pad72)") (class "Default")
      (node (ref "U3") (pin "72") (pinfunction "GPIO26/ECAP3/EQEP2I/MCLKXB_72") (pintype "bidirectional"))
    )
    (net (code "99") (name "unconnected-(U3-GPIO27{slash}ECAP4{slash}EQEP2S{slash}MFSXB-Pad73)") (class "Default")
      (node (ref "U3") (pin "73") (pinfunction "GPIO27/ECAP4/EQEP2S/MFSXB_73") (pintype "bidirectional"))
    )
    (net (code "100") (name "unconnected-(U3-GPIO28{slash}SCIRXDA{slash}XZCS6n-Pad141)") (class "Default")
      (node (ref "U3") (pin "141") (pinfunction "GPIO28/SCIRXDA/XZCS6n_141") (pintype "output"))
    )
    (net (code "101") (name "unconnected-(U3-GPIO32{slash}SDAA{slash}EPWMSYNCI{slash}ADCSOCAOn-Pad74)") (class "Default")
      (node (ref "U3") (pin "74") (pinfunction "GPIO32/SDAA/EPWMSYNCI/ADCSOCAOn_74") (pintype "bidirectional"))
    )
    (net (code "102") (name "unconnected-(U3-GPIO33{slash}SCLA{slash}EPWMSYNCO{slash}ADCSOCBOn-Pad75)") (class "Default")
      (node (ref "U3") (pin "75") (pinfunction "GPIO33/SCLA/EPWMSYNCO/ADCSOCBOn_75") (pintype "bidirectional"))
    )
    (net (code "103") (name "unconnected-(U3-GPIO34{slash}ECAP1{slash}XREADY-Pad142)") (class "Default")
      (node (ref "U3") (pin "142") (pinfunction "GPIO34/ECAP1/XREADY_142") (pintype "input+no_connect"))
    )
    (net (code "104") (name "unconnected-(U3-GPIO35{slash}SCITXDA{slash}XRnW-Pad148)") (class "Default")
      (node (ref "U3") (pin "148") (pinfunction "GPIO35/SCITXDA/XRnW_148") (pintype "output"))
    )
    (net (code "105") (name "unconnected-(U3-GPIO36{slash}SCIRXDA{slash}XZCS0n-Pad145)") (class "Default")
      (node (ref "U3") (pin "145") (pinfunction "GPIO36/SCIRXDA/XZCS0n_145") (pintype "output"))
    )
    (net (code "106") (name "unconnected-(U3-GPIO37{slash}ECAP2{slash}XZCS7n-Pad150)") (class "Default")
      (node (ref "U3") (pin "150") (pinfunction "GPIO37/ECAP2/XZCS7n_150") (pintype "output"))
    )
    (net (code "107") (name "unconnected-(U3-GPIO38{slash}XWE0n-Pad137)") (class "Default")
      (node (ref "U3") (pin "137") (pinfunction "GPIO38/XWE0n_137") (pintype "output"))
    )
    (net (code "108") (name "unconnected-(U3-GPIO39{slash}XA16-Pad175)") (class "Default")
      (node (ref "U3") (pin "175") (pinfunction "GPIO39/XA16_175") (pintype "output"))
    )
    (net (code "109") (name "unconnected-(U3-GPIO40{slash}XA0{slash}XWE1n-Pad151)") (class "Default")
      (node (ref "U3") (pin "151") (pinfunction "GPIO40/XA0/XWE1n_151") (pintype "output"))
    )
    (net (code "110") (name "unconnected-(U3-GPIO41{slash}XA1-Pad152)") (class "Default")
      (node (ref "U3") (pin "152") (pinfunction "GPIO41/XA1_152") (pintype "output"))
    )
    (net (code "111") (name "unconnected-(U3-GPIO42{slash}XA2-Pad153)") (class "Default")
      (node (ref "U3") (pin "153") (pinfunction "GPIO42/XA2_153") (pintype "output"))
    )
    (net (code "112") (name "unconnected-(U3-GPIO43{slash}XA3-Pad156)") (class "Default")
      (node (ref "U3") (pin "156") (pinfunction "GPIO43/XA3_156") (pintype "output"))
    )
    (net (code "113") (name "unconnected-(U3-GPIO44{slash}XA4-Pad157)") (class "Default")
      (node (ref "U3") (pin "157") (pinfunction "GPIO44/XA4_157") (pintype "output"))
    )
    (net (code "114") (name "unconnected-(U3-GPIO45{slash}XA5-Pad158)") (class "Default")
      (node (ref "U3") (pin "158") (pinfunction "GPIO45/XA5_158") (pintype "output"))
    )
    (net (code "115") (name "unconnected-(U3-GPIO46{slash}XA6-Pad161)") (class "Default")
      (node (ref "U3") (pin "161") (pinfunction "GPIO46/XA6_161") (pintype "output"))
    )
    (net (code "116") (name "unconnected-(U3-GPIO47{slash}XA7-Pad162)") (class "Default")
      (node (ref "U3") (pin "162") (pinfunction "GPIO47/XA7_162") (pintype "output"))
    )
    (net (code "117") (name "unconnected-(U3-GPIO64{slash}XD15-Pad115)") (class "Default")
      (node (ref "U3") (pin "115") (pinfunction "GPIO64/XD15_115") (pintype "bidirectional"))
    )
    (net (code "118") (name "unconnected-(U3-GPIO65{slash}XD14-Pad116)") (class "Default")
      (node (ref "U3") (pin "116") (pinfunction "GPIO65/XD14_116") (pintype "bidirectional"))
    )
    (net (code "119") (name "unconnected-(U3-GPIO66{slash}XD13-Pad119)") (class "Default")
      (node (ref "U3") (pin "119") (pinfunction "GPIO66/XD13_119") (pintype "bidirectional"))
    )
    (net (code "120") (name "unconnected-(U3-GPIO67{slash}XD12-Pad122)") (class "Default")
      (node (ref "U3") (pin "122") (pinfunction "GPIO67/XD12_122") (pintype "bidirectional"))
    )
    (net (code "121") (name "unconnected-(U3-GPIO68{slash}XD11-Pad123)") (class "Default")
      (node (ref "U3") (pin "123") (pinfunction "GPIO68/XD11_123") (pintype "bidirectional"))
    )
    (net (code "122") (name "unconnected-(U3-GPIO69{slash}XD10-Pad124)") (class "Default")
      (node (ref "U3") (pin "124") (pinfunction "GPIO69/XD10_124") (pintype "bidirectional"))
    )
    (net (code "123") (name "unconnected-(U3-GPIO78{slash}XD1-Pad135)") (class "Default")
      (node (ref "U3") (pin "135") (pinfunction "GPIO78/XD1_135") (pintype "bidirectional"))
    )
    (net (code "124") (name "unconnected-(U3-GPIO79{slash}XD0-Pad136)") (class "Default")
      (node (ref "U3") (pin "136") (pinfunction "GPIO79/XD0_136") (pintype "bidirectional"))
    )
    (net (code "125") (name "unconnected-(U3-GPIO80{slash}XA8-Pad163)") (class "Default")
      (node (ref "U3") (pin "163") (pinfunction "GPIO80/XA8_163") (pintype "output"))
    )
    (net (code "126") (name "unconnected-(U3-GPIO81{slash}XA9-Pad164)") (class "Default")
      (node (ref "U3") (pin "164") (pinfunction "GPIO81/XA9_164") (pintype "output"))
    )
    (net (code "127") (name "unconnected-(U3-GPIO82{slash}XA10-Pad165)") (class "Default")
      (node (ref "U3") (pin "165") (pinfunction "GPIO82/XA10_165") (pintype "output"))
    )
    (net (code "128") (name "unconnected-(U3-GPIO83{slash}XA11-Pad168)") (class "Default")
      (node (ref "U3") (pin "168") (pinfunction "GPIO83/XA11_168") (pintype "output"))
    )
    (net (code "129") (name "unconnected-(U3-GPIO84{slash}XA12-Pad169)") (class "Default")
      (node (ref "U3") (pin "169") (pinfunction "GPIO84/XA12_169") (pintype "output"))
    )
    (net (code "130") (name "unconnected-(U3-GPIO85{slash}XA13-Pad172)") (class "Default")
      (node (ref "U3") (pin "172") (pinfunction "GPIO85/XA13_172") (pintype "output"))
    )
    (net (code "131") (name "unconnected-(U3-GPIO86{slash}XA14-Pad173)") (class "Default")
      (node (ref "U3") (pin "173") (pinfunction "GPIO86/XA14_173") (pintype "output"))
    )
    (net (code "132") (name "unconnected-(U3-GPIO87{slash}XA15-Pad174)") (class "Default")
      (node (ref "U3") (pin "174") (pinfunction "GPIO87/XA15_174") (pintype "output"))
    )
    (net (code "133") (name "unconnected-(U3-X2-Pad102)") (class "Default")
      (node (ref "U3") (pin "102") (pinfunction "X2_102") (pintype "input+no_connect"))
    )
    (net (code "134") (name "unconnected-(U3-XCLKOUT-Pad138)") (class "Default")
      (node (ref "U3") (pin "138") (pinfunction "XCLKOUT_138") (pintype "output+no_connect"))
    )
    (net (code "135") (name "unconnected-(U3-XRDn-Pad149)") (class "Default")
      (node (ref "U3") (pin "149") (pinfunction "XRDn_149") (pintype "output"))
    )
    (net (code "136") (name "unconnected-(U4-REST-Pad6)") (class "Default")
      (node (ref "U4") (pin "6") (pinfunction "REST_6") (pintype "passive"))
    )
    (net (code "137") (name "unconnected-(X1-NC-Pad1)") (class "Default")
      (node (ref "X1") (pin "1") (pinfunction "NC_1") (pintype "passive"))
    )
  )
)
